# basicUno.net
KiCad netlist of a schematic drawn in EAGLE
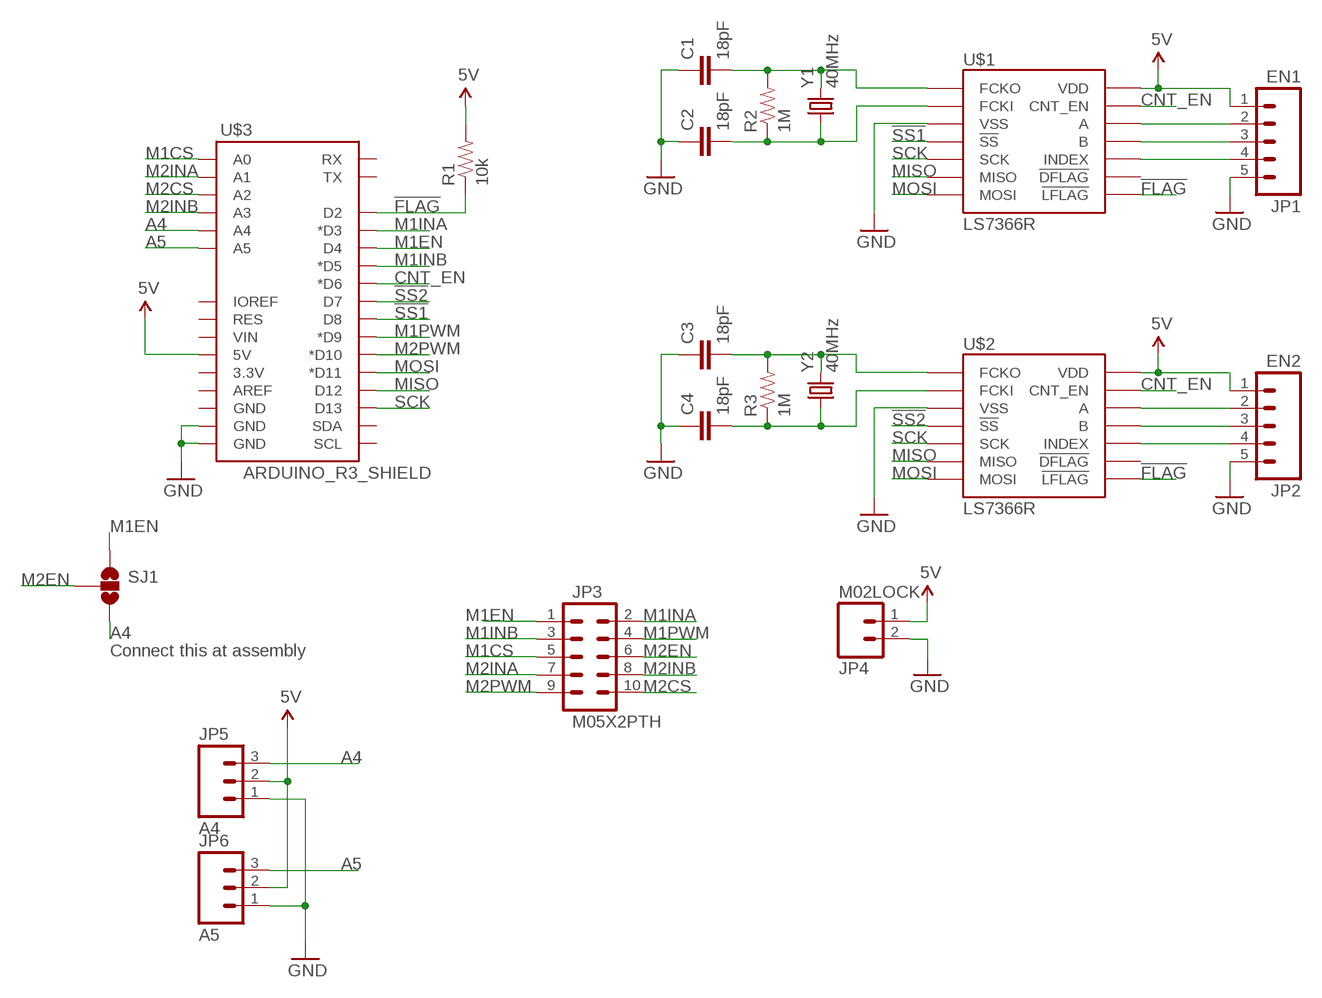
[diagram p0: schematic, sheet 1]

(export (version "E")
  (design (tool "Eeschema 10.0.6"))
  (components
    (comp (ref "C1")
      (value "18pF")
      (footprint "eagle-import:0603-CAP")
      (libsource (lib "eagle-import") (part "CAP0603-CAP"))
    )
    (comp (ref "C2")
      (value "18pF")
      (footprint "eagle-import:0603-CAP")
      (libsource (lib "eagle-import") (part "CAP0603-CAP"))
    )
    (comp (ref "C3")
      (value "18pF")
      (footprint "eagle-import:0603-CAP")
      (libsource (lib "eagle-import") (part "CAP0603-CAP"))
    )
    (comp (ref "C4")
      (value "18pF")
      (footprint "eagle-import:0603-CAP")
      (libsource (lib "eagle-import") (part "CAP0603-CAP"))
    )
    (comp (ref "JP1")
      (value "EN1")
      (footprint "eagle-import:1X05_LOCK")
      (libsource (lib "eagle-import") (part "M05LOCK"))
    )
    (comp (ref "JP2")
      (value "EN2")
      (footprint "eagle-import:1X05_LOCK")
      (libsource (lib "eagle-import") (part "M05LOCK"))
    )
    (comp (ref "JP3")
      (value "M05X2PTH")
      (footprint "eagle-import:AVR_ICSP")
      (libsource (lib "eagle-import") (part "M05X2PTH"))
    )
    (comp (ref "JP4")
      (value "M02LOCK")
      (footprint "eagle-import:1X02_LOCK")
      (libsource (lib "eagle-import") (part "M02LOCK"))
    )
    (comp (ref "JP5")
      (value "A4")
      (footprint "eagle-import:1X03_LOCK")
      (libsource (lib "eagle-import") (part "M03LOCK"))
    )
    (comp (ref "JP6")
      (value "A5")
      (footprint "eagle-import:1X03_LOCK")
      (libsource (lib "eagle-import") (part "M03LOCK"))
    )
    (comp (ref "R1")
      (value "10k")
      (footprint "eagle-import:AXIAL-0.4")
      (libsource (lib "eagle-import") (part "RESISTORPTH-1/4W"))
    )
    (comp (ref "R2")
      (value "1M")
      (footprint "eagle-import:0603-RES")
      (libsource (lib "eagle-import") (part "RESISTOR0603-RES"))
    )
    (comp (ref "R3")
      (value "1M")
      (footprint "eagle-import:0603-RES")
      (libsource (lib "eagle-import") (part "RESISTOR0603-RES"))
    )
    (comp (ref "SJ1")
      (value "SOLDERJUMPER_2WAYT")
      (footprint "eagle-import:SJ_2")
      (libsource (lib "eagle-import") (part "SOLDERJUMPER_2WAYT"))
    )
    (comp (ref "U$1")
      (value "LS7366R")
      (footprint "eagle-import:SOIC14")
      (libsource (lib "eagle-import") (part "LS7366R"))
    )
    (comp (ref "U$2")
      (value "LS7366R")
      (footprint "eagle-import:SOIC14")
      (libsource (lib "eagle-import") (part "LS7366R"))
    )
    (comp (ref "U$3")
      (value "ARDUINO_R3_SHIELD")
      (footprint "eagle-import:UNO_R3_SHIELD")
      (libsource (lib "eagle-import") (part "ARDUINO_R3_SHIELD"))
    )
    (comp (ref "Y1")
      (value "40MHz")
      (footprint "eagle-import:CRYSTAL-SMD-5X3")
      (libsource (lib "eagle-import") (part "CRYSTAL5X3"))
    )
    (comp (ref "Y2")
      (value "40MHz")
      (footprint "eagle-import:CRYSTAL-SMD-5X3")
      (libsource (lib "eagle-import") (part "CRYSTAL5X3"))
    )
  )
  (nets
    (net (code "1") (name "/A4") (class "Default")
      (node (ref "JP5") (pin "3") (pinfunction "3_3") (pintype "passive"))
      (node (ref "SJ1") (pin "3") (pinfunction "3_3") (pintype "passive"))
      (node (ref "U$3") (pin "A4") (pinfunction "A4_A4") (pintype "bidirectional"))
    )
    (net (code "2") (name "/A5") (class "Default")
      (node (ref "JP6") (pin "3") (pinfunction "3_3") (pintype "passive"))
      (node (ref "U$3") (pin "A5") (pinfunction "A5_A5") (pintype "bidirectional"))
    )
    (net (code "3") (name "/CNT_EN") (class "Default")
      (node (ref "U$1") (pin "13") (pinfunction "CNT_EN_13") (pintype "bidirectional"))
      (node (ref "U$2") (pin "13") (pinfunction "CNT_EN_13") (pintype "bidirectional"))
      (node (ref "U$3") (pin "D6") (pinfunction "*D6_D6") (pintype "bidirectional"))
    )
    (net (code "4") (name "/M1CS") (class "Default")
      (node (ref "JP3") (pin "5") (pinfunction "5_5") (pintype "passive"))
      (node (ref "U$3") (pin "A0") (pinfunction "A0_A0") (pintype "bidirectional"))
    )
    (net (code "5") (name "/M1EN") (class "Default")
      (node (ref "JP3") (pin "1") (pinfunction "1_1") (pintype "passive"))
      (node (ref "SJ1") (pin "1") (pinfunction "1_1") (pintype "passive"))
      (node (ref "U$3") (pin "D4") (pinfunction "D4_D4") (pintype "bidirectional"))
    )
    (net (code "6") (name "/M1INA") (class "Default")
      (node (ref "JP3") (pin "2") (pinfunction "2_2") (pintype "passive"))
      (node (ref "U$3") (pin "D3") (pinfunction "*D3_D3") (pintype "bidirectional"))
    )
    (net (code "7") (name "/M1INB") (class "Default")
      (node (ref "JP3") (pin "3") (pinfunction "3_3") (pintype "passive"))
      (node (ref "U$3") (pin "D5") (pinfunction "*D5_D5") (pintype "bidirectional"))
    )
    (net (code "8") (name "/M1PWM") (class "Default")
      (node (ref "JP3") (pin "4") (pinfunction "4_4") (pintype "passive"))
      (node (ref "U$3") (pin "D9") (pinfunction "*D9_D9") (pintype "bidirectional"))
    )
    (net (code "9") (name "/M2CS") (class "Default")
      (node (ref "JP3") (pin "10") (pinfunction "10_10") (pintype "passive"))
      (node (ref "U$3") (pin "A2") (pinfunction "A2_A2") (pintype "bidirectional"))
    )
    (net (code "10") (name "/M2EN") (class "Default")
      (node (ref "JP3") (pin "6") (pinfunction "6_6") (pintype "passive"))
      (node (ref "SJ1") (pin "2") (pinfunction "2_2") (pintype "passive"))
    )
    (net (code "11") (name "/M2INA") (class "Default")
      (node (ref "JP3") (pin "7") (pinfunction "7_7") (pintype "passive"))
      (node (ref "U$3") (pin "A1") (pinfunction "A1_A1") (pintype "bidirectional"))
    )
    (net (code "12") (name "/M2INB") (class "Default")
      (node (ref "JP3") (pin "8") (pinfunction "8_8") (pintype "passive"))
      (node (ref "U$3") (pin "A3") (pinfunction "A3_A3") (pintype "bidirectional"))
    )
    (net (code "13") (name "/M2PWM") (class "Default")
      (node (ref "JP3") (pin "9") (pinfunction "9_9") (pintype "passive"))
      (node (ref "U$3") (pin "D10") (pinfunction "*D10_D10") (pintype "bidirectional"))
    )
    (net (code "14") (name "/MISO") (class "Default")
      (node (ref "U$1") (pin "6") (pinfunction "MISO_6") (pintype "bidirectional"))
      (node (ref "U$2") (pin "6") (pinfunction "MISO_6") (pintype "bidirectional"))
      (node (ref "U$3") (pin "D12") (pinfunction "D12_D12") (pintype "bidirectional"))
    )
    (net (code "15") (name "/MOSI") (class "Default")
      (node (ref "U$1") (pin "7") (pinfunction "MOSI_7") (pintype "bidirectional"))
      (node (ref "U$2") (pin "7") (pinfunction "MOSI_7") (pintype "bidirectional"))
      (node (ref "U$3") (pin "D11") (pinfunction "*D11_D11") (pintype "bidirectional"))
    )
    (net (code "16") (name "/SCK") (class "Default")
      (node (ref "U$1") (pin "5") (pinfunction "SCK_5") (pintype "bidirectional"))
      (node (ref "U$2") (pin "5") (pinfunction "SCK_5") (pintype "bidirectional"))
      (node (ref "U$3") (pin "D13") (pinfunction "D13_D13") (pintype "bidirectional"))
    )
    (net (code "17") (name "/~{FLAG}") (class "Default")
      (node (ref "R1") (pin "P$1") (pinfunction "1_P$1") (pintype "passive"))
      (node (ref "U$1") (pin "8") (pinfunction "~{LFLAG}_8") (pintype "bidirectional"))
      (node (ref "U$2") (pin "8") (pinfunction "~{LFLAG}_8") (pintype "bidirectional"))
      (node (ref "U$3") (pin "D2") (pinfunction "D2_D2") (pintype "bidirectional"))
    )
    (net (code "18") (name "/~{SS1}") (class "Default")
      (node (ref "U$1") (pin "4") (pinfunction "~{SS}_4") (pintype "bidirectional"))
      (node (ref "U$3") (pin "D8") (pinfunction "D8_D8") (pintype "bidirectional"))
    )
    (net (code "19") (name "/~{SS2}") (class "Default")
      (node (ref "U$2") (pin "4") (pinfunction "~{SS}_4") (pintype "bidirectional"))
      (node (ref "U$3") (pin "D7") (pinfunction "D7_D7") (pintype "bidirectional"))
    )
    (net (code "20") (name "5V") (class "Default")
      (node (ref "JP1") (pin "1") (pinfunction "1_1") (pintype "passive"))
      (node (ref "JP2") (pin "1") (pinfunction "1_1") (pintype "passive"))
      (node (ref "JP4") (pin "1") (pinfunction "1_1") (pintype "passive"))
      (node (ref "JP5") (pin "2") (pinfunction "2_2") (pintype "passive"))
      (node (ref "JP6") (pin "2") (pinfunction "2_2") (pintype "passive"))
      (node (ref "R1") (pin "P$2") (pinfunction "2_P$2") (pintype "passive"))
      (node (ref "U$1") (pin "14") (pinfunction "VDD_14") (pintype "bidirectional"))
      (node (ref "U$2") (pin "14") (pinfunction "VDD_14") (pintype "bidirectional"))
      (node (ref "U$3") (pin "5V") (pinfunction "5V_5V") (pintype "bidirectional"))
    )
    (net (code "21") (name "GND") (class "Default")
      (node (ref "C1") (pin "1") (pinfunction "1_1") (pintype "passive"))
      (node (ref "C2") (pin "1") (pinfunction "1_1") (pintype "passive"))
      (node (ref "C3") (pin "1") (pinfunction "1_1") (pintype "passive"))
      (node (ref "C4") (pin "1") (pinfunction "1_1") (pintype "passive"))
      (node (ref "JP1") (pin "5") (pinfunction "5_5") (pintype "passive"))
      (node (ref "JP2") (pin "5") (pinfunction "5_5") (pintype "passive"))
      (node (ref "JP4") (pin "2") (pinfunction "2_2") (pintype "passive"))
      (node (ref "JP5") (pin "1") (pinfunction "1_1") (pintype "passive"))
      (node (ref "JP6") (pin "1") (pinfunction "1_1") (pintype "passive"))
      (node (ref "U$1") (pin "3") (pinfunction "VSS_3") (pintype "bidirectional"))
      (node (ref "U$2") (pin "3") (pinfunction "VSS_3") (pintype "bidirectional"))
      (node (ref "U$3") (pin "GND@0") (pinfunction "GND_GND@0") (pintype "bidirectional"))
      (node (ref "U$3") (pin "GND@1") (pinfunction "GND_GND@1") (pintype "bidirectional"))
    )
    (net (code "22") (name "Net-(U$1-A)") (class "Default")
      (node (ref "JP1") (pin "2") (pinfunction "2_2") (pintype "passive"))
      (node (ref "U$1") (pin "12") (pinfunction "A_12") (pintype "bidirectional"))
    )
    (net (code "23") (name "Net-(U$1-B)") (class "Default")
      (node (ref "JP1") (pin "3") (pinfunction "3_3") (pintype "passive"))
      (node (ref "U$1") (pin "11") (pinfunction "B_11") (pintype "bidirectional"))
    )
    (net (code "24") (name "Net-(U$1-FCKI)") (class "Default")
      (node (ref "C2") (pin "2") (pinfunction "2_2") (pintype "passive"))
      (node (ref "R2") (pin "1") (pinfunction "1_1") (pintype "passive"))
      (node (ref "U$1") (pin "2") (pinfunction "FCKI_2") (pintype "bidirectional"))
      (node (ref "Y1") (pin "1") (pinfunction "1_1") (pintype "passive"))
    )
    (net (code "25") (name "Net-(U$1-FCKO)") (class "Default")
      (node (ref "C1") (pin "2") (pinfunction "2_2") (pintype "passive"))
      (node (ref "R2") (pin "2") (pinfunction "2_2") (pintype "passive"))
      (node (ref "U$1") (pin "1") (pinfunction "FCKO_1") (pintype "bidirectional"))
      (node (ref "Y1") (pin "3") (pinfunction "2_3") (pintype "passive"))
    )
    (net (code "26") (name "Net-(U$1-INDEX)") (class "Default")
      (node (ref "JP1") (pin "4") (pinfunction "4_4") (pintype "passive"))
      (node (ref "U$1") (pin "10") (pinfunction "INDEX_10") (pintype "bidirectional"))
    )
    (net (code "27") (name "Net-(U$2-A)") (class "Default")
      (node (ref "JP2") (pin "2") (pinfunction "2_2") (pintype "passive"))
      (node (ref "U$2") (pin "12") (pinfunction "A_12") (pintype "bidirectional"))
    )
    (net (code "28") (name "Net-(U$2-B)") (class "Default")
      (node (ref "JP2") (pin "3") (pinfunction "3_3") (pintype "passive"))
      (node (ref "U$2") (pin "11") (pinfunction "B_11") (pintype "bidirectional"))
    )
    (net (code "29") (name "Net-(U$2-FCKI)") (class "Default")
      (node (ref "C4") (pin "2") (pinfunction "2_2") (pintype "passive"))
      (node (ref "R3") (pin "1") (pinfunction "1_1") (pintype "passive"))
      (node (ref "U$2") (pin "2") (pinfunction "FCKI_2") (pintype "bidirectional"))
      (node (ref "Y2") (pin "1") (pinfunction "1_1") (pintype "passive"))
    )
    (net (code "30") (name "Net-(U$2-FCKO)") (class "Default")
      (node (ref "C3") (pin "2") (pinfunction "2_2") (pintype "passive"))
      (node (ref "R3") (pin "2") (pinfunction "2_2") (pintype "passive"))
      (node (ref "U$2") (pin "1") (pinfunction "FCKO_1") (pintype "bidirectional"))
      (node (ref "Y2") (pin "3") (pinfunction "2_3") (pintype "passive"))
    )
    (net (code "31") (name "Net-(U$2-INDEX)") (class "Default")
      (node (ref "JP2") (pin "4") (pinfunction "4_4") (pintype "passive"))
      (node (ref "U$2") (pin "10") (pinfunction "INDEX_10") (pintype "bidirectional"))
    )
    (net (code "32") (name "unconnected-(U$1-~{DFLAG}-Pad9)") (class "Default")
      (node (ref "U$1") (pin "9") (pinfunction "~{DFLAG}_9") (pintype "bidirectional"))
    )
    (net (code "33") (name "unconnected-(U$2-~{DFLAG}-Pad9)") (class "Default")
      (node (ref "U$2") (pin "9") (pinfunction "~{DFLAG}_9") (pintype "bidirectional"))
    )
    (net (code "34") (name "unconnected-(U$3-GND-PadGND@2)") (class "Default")
      (node (ref "U$3") (pin "GND@2") (pinfunction "GND_GND@2") (pintype "bidirectional"))
    )
    (net (code "35") (name "unconnected-(U$3-Pad3.3V)") (class "Default")
      (node (ref "U$3") (pin "3.3V") (pinfunction "3.3V_3.3V") (pintype "bidirectional"))
    )
    (net (code "36") (name "unconnected-(U$3-PadAREF)") (class "Default")
      (node (ref "U$3") (pin "AREF") (pinfunction "AREF_AREF") (pintype "bidirectional"))
    )
    (net (code "37") (name "unconnected-(U$3-PadIOREF)") (class "Default")
      (node (ref "U$3") (pin "IOREF") (pinfunction "IOREF_IOREF") (pintype "bidirectional"))
    )
    (net (code "38") (name "unconnected-(U$3-PadRES)") (class "Default")
      (node (ref "U$3") (pin "RES") (pinfunction "RES_RES") (pintype "bidirectional"))
    )
    (net (code "39") (name "unconnected-(U$3-PadRX)") (class "Default")
      (node (ref "U$3") (pin "RX") (pinfunction "RX_RX") (pintype "bidirectional"))
    )
    (net (code "40") (name "unconnected-(U$3-PadSCL)") (class "Default")
      (node (ref "U$3") (pin "SCL") (pinfunction "SCL_SCL") (pintype "bidirectional"))
    )
    (net (code "41") (name "unconnected-(U$3-PadSDA)") (class "Default")
      (node (ref "U$3") (pin "SDA") (pinfunction "SDA_SDA") (pintype "bidirectional"))
    )
    (net (code "42") (name "unconnected-(U$3-PadTX)") (class "Default")
      (node (ref "U$3") (pin "TX") (pinfunction "TX_TX") (pintype "bidirectional"))
    )
    (net (code "43") (name "unconnected-(U$3-PadVIN)") (class "Default")
      (node (ref "U$3") (pin "VIN") (pinfunction "VIN_VIN") (pintype "bidirectional"))
    )
  )
)
